# 02-Power.net
KiCad netlist of a schematic drawn in Altium Designer
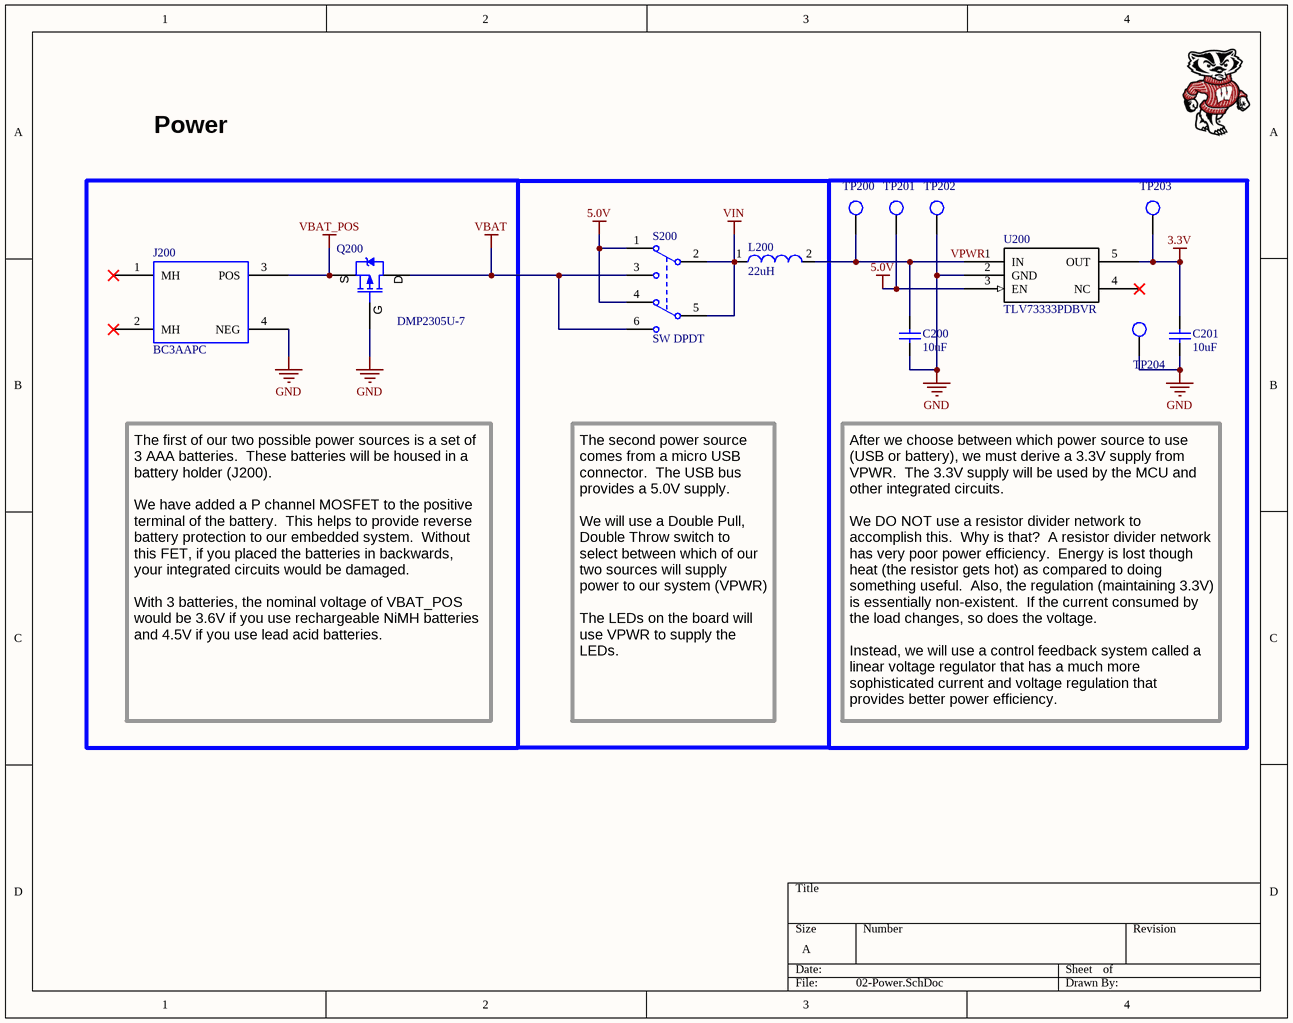
[diagram p0: 02-Power.SchDoc]

(export (version "E")
  (design (tool "Eeschema 10.0.6"))
  (components
    (comp (ref "C200")
      (value "10uF")
      (footprint "CAP_0805")
      (description "CAP CER 10UF 16V X7R 0805")
      (fields
        (field (name "MANUFACTURER") "Samsung")
        (field (name "MANUFACTURER PART NUMBER") "CL21A106KPCLQNC")
        (field (name "CAPACITANCE") "10uF")
      )
      (libsource (lib "ece315-S20") (part "CAP_0805_U_010.00"))
    )
    (comp (ref "C201")
      (value "10uF")
      (footprint "CAP_0805")
      (description "CAP CER 10UF 16V X7R 0805")
      (fields
        (field (name "MANUFACTURER") "Samsung")
        (field (name "MANUFACTURER PART NUMBER") "CL21A106KPCLQNC")
        (field (name "CAPACITANCE") "10uF")
      )
      (libsource (lib "ece315-S20") (part "CAP_0805_U_010.00"))
    )
    (comp (ref "J200")
      (value "BC3AAPC")
      (footprint "BC3AAPC")
      (description "BATTERY HOLDER AA 3 CELL PC PIN")
      (fields
        (field (name "MANUFACTURER") "Memory Protection Devices")
        (field (name "MANUFACTURER PART NUMBER") "BC3AAPC")
      )
      (libsource (lib "Battery") (part "BC3AAPC"))
    )
    (comp (ref "L200")
      (value "SRN3015-220M")
      (footprint "SRN3015")
      (description "22uH 3x3mm sheilded inductor 600mA")
      (fields (field (name "TOLERANCE") "20%") (field (name "INDUCTANCE") "22uH"))
      (libsource (lib "Inductors") (part "SRN3015-220M"))
    )
    (comp (ref "Q200")
      (value "PMOS-DMP2305U-7")
      (footprint "SOT23")
      (description "MOSFET P-CH 20V 4.2A SOT-23")
      (fields
        (field (name "MANUFACTURER") "Diodes Zetex")
        (field (name "MANUFACTURER PART NUMBER") "DMP2305U-7")
      )
      (libsource (lib "Transistors") (part "PMOS-DMP2305U-7"))
    )
    (comp (ref "S200")
      (value "SW DPDT")
      (footprint "DPDT")
      (description "Switch")
      (fields
        (field (name "MANUFACTURER") "ITT /  C&K Components")
        (field (name "MANUFACTURER PART NUMBER") "JS202011SCQN")
        (field (name "PUBLISHER") "Altium Limited")
      )
      (libsource (lib "ece315-2018-fall") (part "SW DPDT"))
    )
    (comp (ref "TP200")
      (value "TP_1206")
      (footprint "TP-SMC-1206")
      (description "Test Point SMD 1206")
      (fields
        (field (name "MANUFACTURER") "TE Connectivity (Tyco Electronics)")
        (field (name "MANUFACTURER PART NUMBER") "1625854-1")
      )
      (libsource (lib "ece315-S20") (part "TP_1206"))
    )
    (comp (ref "TP201")
      (value "TP_1206")
      (footprint "TP-SMC-1206")
      (description "Test Point SMD 1206")
      (fields
        (field (name "MANUFACTURER") "TE Connectivity (Tyco Electronics)")
        (field (name "MANUFACTURER PART NUMBER") "1625854-1")
      )
      (libsource (lib "ece315-S20") (part "TP_1206"))
    )
    (comp (ref "TP202")
      (value "TP_1206")
      (footprint "TP-SMC-1206")
      (description "Test Point SMD 1206")
      (fields
        (field (name "MANUFACTURER") "TE Connectivity (Tyco Electronics)")
        (field (name "MANUFACTURER PART NUMBER") "1625854-1")
      )
      (libsource (lib "ece315-S20") (part "TP_1206"))
    )
    (comp (ref "TP203")
      (value "TP_1206")
      (footprint "TP-SMC-1206")
      (description "Test Point SMD 1206")
      (fields
        (field (name "MANUFACTURER") "TE Connectivity (Tyco Electronics)")
        (field (name "MANUFACTURER PART NUMBER") "1625854-1")
      )
      (libsource (lib "ece315-S20") (part "TP_1206"))
    )
    (comp (ref "TP204")
      (value "TP_1206")
      (footprint "TP-SMC-1206")
      (description "Test Point SMD 1206")
      (fields
        (field (name "MANUFACTURER") "TE Connectivity (Tyco Electronics)")
        (field (name "MANUFACTURER PART NUMBER") "1625854-1")
      )
      (libsource (lib "ece315-S20") (part "TP_1206"))
    )
    (comp (ref "U200")
      (value "IC-TLV733P")
      (footprint "IC_TLV73333")
      (description "IC REG LINEAR 3.3V 300MA SOT23-5")
      (fields
        (field (name "MANUFACTURER") "Texas Instruments")
        (field (name "MANUFACTURER PART NUMBER") "TLV73333PDBVR")
      )
      (libsource (lib "ece315-S20") (part "IC-TLV733P"))
    )
  )
  (nets
    (net (code "1") (name "/VPWR") (class "Default")
      (node (ref "C200") (pin "2") (pinfunction "2_2") (pintype "passive"))
      (node (ref "L200") (pin "2") (pinfunction "1_2") (pintype "passive"))
      (node (ref "TP200") (pin "1") (pintype "passive"))
      (node (ref "U200") (pin "1") (pinfunction "IN_1") (pintype "power_in"))
    )
    (net (code "2") (name "3.3V") (class "Default")
      (node (ref "C201") (pin "2") (pinfunction "2_2") (pintype "passive"))
      (node (ref "TP203") (pin "1") (pintype "passive"))
      (node (ref "U200") (pin "5") (pinfunction "OUT_5") (pintype "power_in"))
    )
    (net (code "3") (name "5.0V") (class "Default")
      (node (ref "S200") (pin "1") (pinfunction "NC1_1") (pintype "passive"))
      (node (ref "S200") (pin "4") (pinfunction "NC2_4") (pintype "passive"))
      (node (ref "TP201") (pin "1") (pintype "passive"))
      (node (ref "U200") (pin "3") (pinfunction "EN_3") (pintype "input"))
    )
    (net (code "4") (name "GND") (class "Default")
      (node (ref "C200") (pin "1") (pinfunction "1_1") (pintype "passive"))
      (node (ref "C201") (pin "1") (pinfunction "1_1") (pintype "passive"))
      (node (ref "J200") (pin "4") (pinfunction "NEG_4") (pintype "power_in"))
      (node (ref "Q200") (pin "1") (pinfunction "G_1") (pintype "passive"))
      (node (ref "TP202") (pin "1") (pintype "passive"))
      (node (ref "TP204") (pin "1") (pintype "passive"))
      (node (ref "U200") (pin "2") (pinfunction "GND_2") (pintype "power_in"))
    )
    (net (code "5") (name "VBAT") (class "Default")
      (node (ref "Q200") (pin "3") (pinfunction "D_3") (pintype "passive"))
      (node (ref "S200") (pin "3") (pinfunction "NO1_3") (pintype "passive"))
      (node (ref "S200") (pin "6") (pinfunction "NO2_6") (pintype "passive"))
    )
    (net (code "6") (name "VBAT_POS") (class "Default")
      (node (ref "J200") (pin "3") (pinfunction "POS_3") (pintype "power_in"))
      (node (ref "Q200") (pin "2") (pinfunction "S_2") (pintype "passive"))
    )
    (net (code "7") (name "VIN") (class "Default")
      (node (ref "L200") (pin "1") (pinfunction "0_1") (pintype "passive"))
      (node (ref "S200") (pin "2") (pinfunction "COMMON1_2") (pintype "passive"))
      (node (ref "S200") (pin "5") (pinfunction "COMMON2_5") (pintype "passive"))
    )
    (net (code "8") (name "unconnected-(J200-MH-Pad1)") (class "Default")
      (node (ref "J200") (pin "1") (pinfunction "MH_1") (pintype "passive+no_connect"))
    )
    (net (code "9") (name "unconnected-(J200-MH-Pad2)") (class "Default")
      (node (ref "J200") (pin "2") (pinfunction "MH_2") (pintype "passive+no_connect"))
    )
    (net (code "10") (name "unconnected-(U200-NC-Pad4)") (class "Default")
      (node (ref "U200") (pin "4") (pinfunction "NC_4") (pintype "passive+no_connect"))
    )
  )
)
